# 3_diplom.net
KiCad netlist of a schematic drawn in Altium Designer
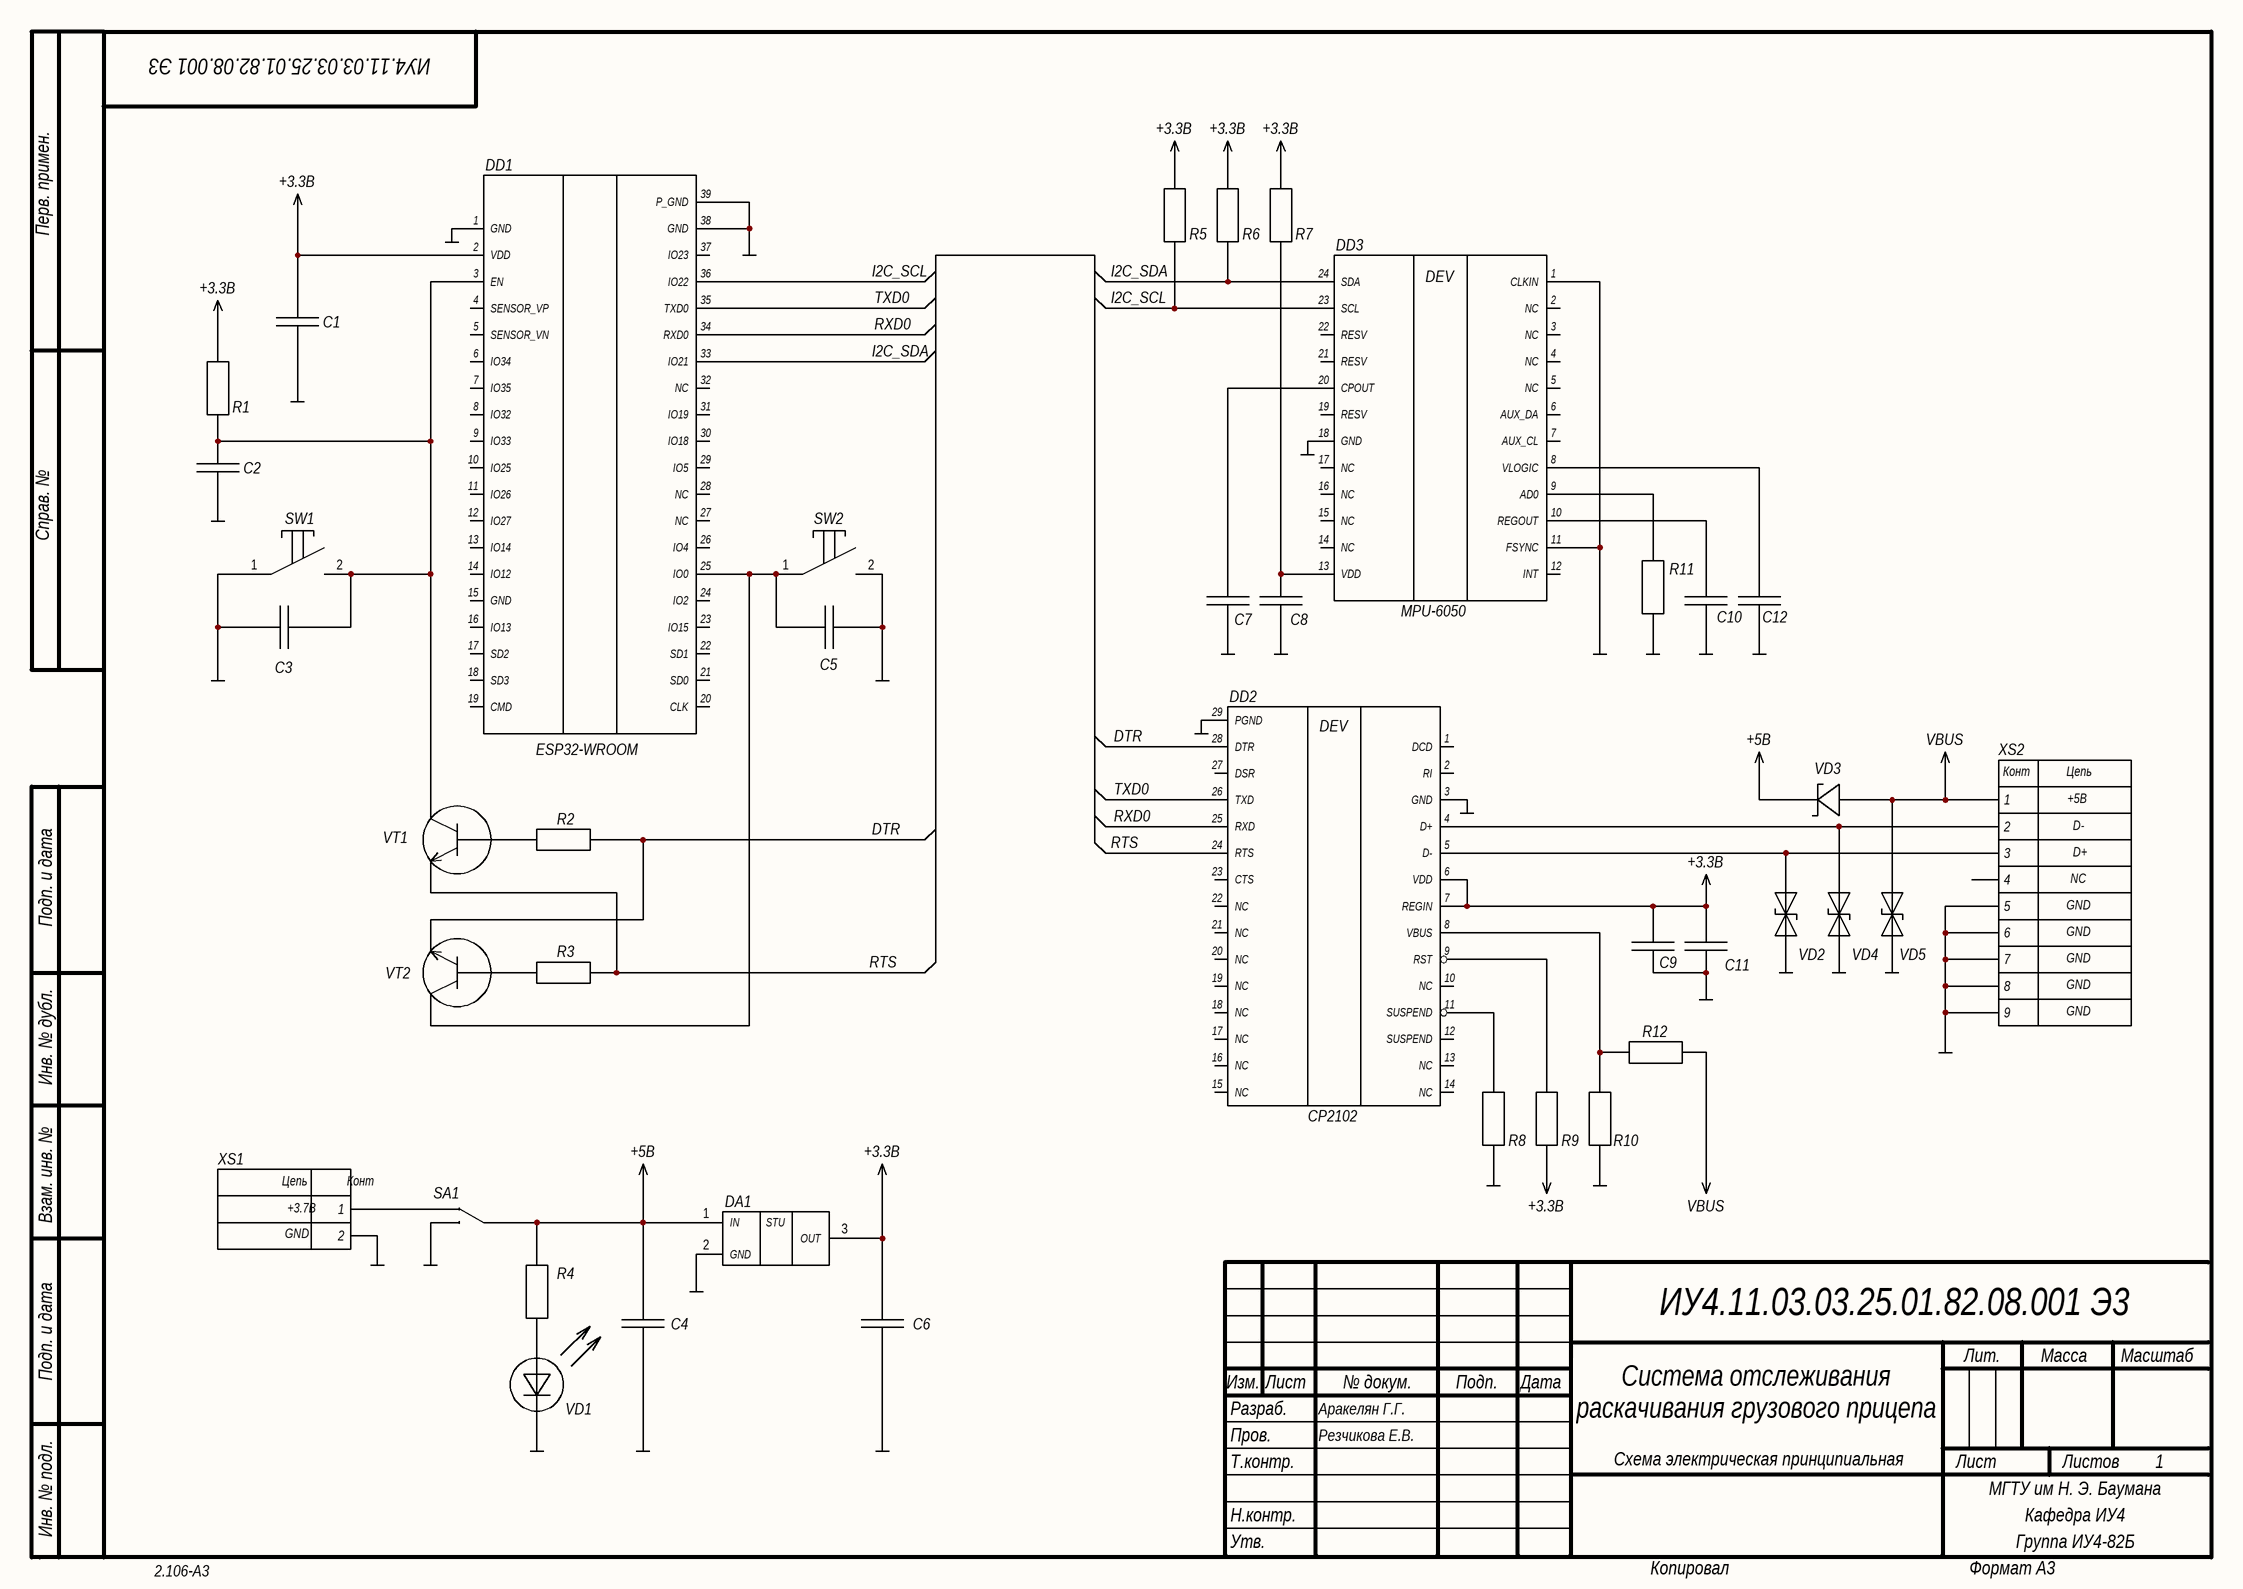
[diagram p0: Э3_diplom.SchDoc]

(export (version "E")
  (design (tool "Eeschema 10.0.6"))
  (components
    (comp (ref "C1") (value "~") (footprint "CAP: 0805") (libsource (lib "diplom") (part "Cap")))
    (comp (ref "C2") (value "~") (footprint "CAP: 0805") (libsource (lib "diplom") (part "Cap")))
    (comp (ref "C3") (value "~") (footprint "CAP: 0805") (libsource (lib "diplom") (part "Cap")))
    (comp (ref "C4") (value "~") (footprint "CAP: 0805") (libsource (lib "diplom") (part "Cap")))
    (comp (ref "C5") (value "~") (footprint "CAP: 0805") (libsource (lib "diplom") (part "Cap")))
    (comp (ref "C6") (value "~") (footprint "CAP: 0805") (libsource (lib "diplom") (part "Cap")))
    (comp (ref "C7") (value "~") (footprint "CAP: 0805") (libsource (lib "diplom") (part "Cap")))
    (comp (ref "C8") (value "~") (footprint "CAP: 0805") (libsource (lib "diplom") (part "Cap")))
    (comp (ref "C9") (value "~") (footprint "CAP: 0805") (libsource (lib "diplom") (part "Cap")))
    (comp (ref "C10") (value "~") (footprint "CAP: 0805") (libsource (lib "diplom") (part "Cap")))
    (comp (ref "C11") (value "~") (footprint "CAP: 0805") (libsource (lib "diplom") (part "Cap")))
    (comp (ref "C12") (value "~") (footprint "CAP: 0805") (libsource (lib "diplom") (part "Cap")))
    (comp (ref "DA1")
      (value "AP2138N")
      (footprint "SOT-23")
      (fields (field (name "PUBLISHER") "Andrew Danich"))
      (libsource (lib "diplom") (part "DC-DC 3.3V"))
    )
    (comp (ref "DD1")
      (value "ESP32-WROOM")
      (footprint "ESP32-S3-WROOM-1-N16R2 - duplicate")
      (libsource (lib "diplom") (part "ESP32-WROVER-B"))
    )
    (comp (ref "DD2") (value "CP2102") (footprint "CP2102") (libsource (lib "diplom") (part "CP2102")))
    (comp (ref "DD3") (value "MPU-6050") (footprint "MPU-6050") (libsource (lib "diplom") (part "MPU-6050")))
    (comp (ref "R1") (value "~") (footprint "RES: 0805") (libsource (lib "diplom") (part "res")))
    (comp (ref "R2") (value "~") (footprint "RES: 0805") (libsource (lib "diplom") (part "res")))
    (comp (ref "R3") (value "~") (footprint "RES: 0805") (libsource (lib "diplom") (part "res")))
    (comp (ref "R4") (value "~") (footprint "RES: 0805") (libsource (lib "diplom") (part "res")))
    (comp (ref "R5") (value "~") (footprint "RES: 0805") (libsource (lib "") (part "res_1")))
    (comp (ref "R6") (value "~") (footprint "RES: 0805") (libsource (lib "") (part "res_1")))
    (comp (ref "R7") (value "~") (footprint "RES: 0805") (libsource (lib "") (part "res_1")))
    (comp (ref "R8") (value "~") (footprint "RES: 0805") (libsource (lib "diplom") (part "res")))
    (comp (ref "R9") (value "~") (footprint "RES: 0805") (libsource (lib "diplom") (part "res")))
    (comp (ref "R10") (value "~") (footprint "RES: 0805") (libsource (lib "diplom") (part "res")))
    (comp (ref "R11") (value "~") (footprint "RES: 0805") (libsource (lib "diplom") (part "res")))
    (comp (ref "R12") (value "~") (footprint "RES: 0805") (libsource (lib "diplom") (part "res")))
    (comp (ref "SA1")
      (value "Switch ON-ON")
      (footprint "PcbLib1:BUT: MTS-102")
      (description "Switch, ON-ON")
      (fields (field (name "MANUFACTURER") "Jietong Switch") (field (name "PARTNUMBER") "MTC-102"))
      (libsource (lib "diplom") (part "Switch ON-ON"))
    )
    (comp (ref "SW1")
      (value "Button")
      (footprint "BUT: SMD 6x6 H4.3")
      (libsource (lib "diplom") (part "Button"))
    )
    (comp (ref "SW2")
      (value "Button")
      (footprint "BUT: SMD 6x6 H4.3")
      (libsource (lib "diplom") (part "Button"))
    )
    (comp (ref "VD1") (value "~") (footprint "LED: 0805") (libsource (lib "diplom") (part "LED")))
    (comp (ref "VD2")
      (value "Suppressor-Bi")
      (footprint "DIOD-523")
      (fields (field (name "PUBLISHER") "Andrew Danich"))
      (libsource (lib "diplom") (part "Suppressor-Bi"))
    )
    (comp (ref "VD3")
      (value "Stab")
      (footprint "BAT760-7")
      (fields (field (name "PUBLISHER") "Andrew Danich"))
      (libsource (lib "diplom") (part "Stab"))
    )
    (comp (ref "VD4")
      (value "Suppressor-Bi")
      (footprint "DIOD-523")
      (fields (field (name "PUBLISHER") "Andrew Danich"))
      (libsource (lib "diplom") (part "Suppressor-Bi"))
    )
    (comp (ref "VD5")
      (value "Suppressor-Bi")
      (footprint "DIOD-523")
      (fields (field (name "PUBLISHER") "Andrew Danich"))
      (libsource (lib "diplom") (part "Suppressor-Bi"))
    )
    (comp (ref "VT1")
      (value "BJT-NPN")
      (footprint "SOT-23")
      (fields (field (name "PUBLISHER") "Andrew Danich"))
      (libsource (lib "diplom") (part "BJT-NPN"))
    )
    (comp (ref "VT2")
      (value "BJT-NPN")
      (footprint "SOT-23")
      (fields (field (name "PUBLISHER") "Andrew Danich"))
      (libsource (lib "diplom") (part "BJT-NPN"))
    )
    (comp (ref "XS1") (value "bat") (footprint "Li-Po") (libsource (lib "diplom") (part "bat")))
    (comp (ref "XS2") (value "USB con") (footprint "MicroUSB") (libsource (lib "diplom") (part "Micro USB")))
  )
  (nets
    (net (code "1") (name "+3.3В") (class "Default")
      (node (ref "C1") (pin "1") (pinfunction "1_1") (pintype "passive"))
      (node (ref "C11") (pin "1") (pinfunction "1_1") (pintype "passive"))
      (node (ref "C6") (pin "1") (pinfunction "1_1") (pintype "passive"))
      (node (ref "C9") (pin "1") (pinfunction "1_1") (pintype "passive"))
      (node (ref "DA1") (pin "3") (pinfunction "OUT_3") (pintype "passive"))
      (node (ref "DD1") (pin "2") (pinfunction "VDD_2") (pintype "passive"))
      (node (ref "DD2") (pin "6") (pinfunction "VDD_6") (pintype "passive"))
      (node (ref "DD2") (pin "7") (pinfunction "REGIN_7") (pintype "passive"))
      (node (ref "R1") (pin "1") (pinfunction "1_1") (pintype "passive"))
      (node (ref "R5") (pin "1") (pinfunction "1_1") (pintype "passive"))
      (node (ref "R6") (pin "1") (pinfunction "1_1") (pintype "passive"))
      (node (ref "R7") (pin "1") (pinfunction "1_1") (pintype "passive"))
      (node (ref "R9") (pin "2") (pinfunction "2_2") (pintype "passive"))
    )
    (net (code "2") (name "+5В") (class "Default")
      (node (ref "C4") (pin "1") (pinfunction "1_1") (pintype "passive"))
      (node (ref "DA1") (pin "1") (pinfunction "IN_1") (pintype "passive"))
      (node (ref "R4") (pin "1") (pinfunction "1_1") (pintype "passive"))
      (node (ref "SA1") (pin "2") (pinfunction "PIN0_2") (pintype "passive"))
      (node (ref "VD3") (pin "2") (pinfunction "К_2") (pintype "passive"))
    )
    (net (code "3") (name "/DTR") (class "Default")
      (node (ref "DD2") (pin "28") (pinfunction "DTR_28") (pintype "passive"))
      (node (ref "R2") (pin "1") (pinfunction "1_1") (pintype "passive"))
      (node (ref "VT2") (pin "3") (pinfunction "Э_3") (pintype "passive"))
    )
    (net (code "4") (name "/I2C_SCL") (class "Default")
      (node (ref "DD1") (pin "36") (pinfunction "IO22_36") (pintype "passive"))
      (node (ref "DD3") (pin "23") (pinfunction "SCL_23") (pintype "passive"))
      (node (ref "R5") (pin "2") (pinfunction "2_2") (pintype "passive"))
    )
    (net (code "5") (name "/I2C_SDA") (class "Default")
      (node (ref "DD1") (pin "33") (pinfunction "IO21_33") (pintype "passive"))
      (node (ref "DD3") (pin "24") (pinfunction "SDA_24") (pintype "passive"))
      (node (ref "R6") (pin "2") (pinfunction "2_2") (pintype "passive"))
    )
    (net (code "6") (name "/RTS") (class "Default")
      (node (ref "DD2") (pin "24") (pinfunction "RTS_24") (pintype "passive"))
      (node (ref "R3") (pin "1") (pinfunction "1_1") (pintype "passive"))
      (node (ref "VT1") (pin "3") (pinfunction "Э_3") (pintype "passive"))
    )
    (net (code "7") (name "/RXD0") (class "Default")
      (node (ref "DD1") (pin "34") (pinfunction "RXD0_34") (pintype "passive"))
      (node (ref "DD2") (pin "25") (pinfunction "RXD_25") (pintype "passive"))
    )
    (net (code "8") (name "/TXD0") (class "Default")
      (node (ref "DD1") (pin "35") (pinfunction "TXD0_35") (pintype "passive"))
      (node (ref "DD2") (pin "26") (pinfunction "TXD_26") (pintype "passive"))
    )
    (net (code "9") (name "GND") (class "Default")
      (node (ref "C1") (pin "2") (pinfunction "2_2") (pintype "passive"))
      (node (ref "C10") (pin "2") (pinfunction "2_2") (pintype "passive"))
      (node (ref "C11") (pin "2") (pinfunction "2_2") (pintype "passive"))
      (node (ref "C12") (pin "2") (pinfunction "2_2") (pintype "passive"))
      (node (ref "C2") (pin "2") (pinfunction "2_2") (pintype "passive"))
      (node (ref "C3") (pin "1") (pinfunction "1_1") (pintype "passive"))
      (node (ref "C4") (pin "2") (pinfunction "2_2") (pintype "passive"))
      (node (ref "C5") (pin "2") (pinfunction "2_2") (pintype "passive"))
      (node (ref "C6") (pin "2") (pinfunction "2_2") (pintype "passive"))
      (node (ref "C7") (pin "2") (pinfunction "2_2") (pintype "passive"))
      (node (ref "C8") (pin "2") (pinfunction "2_2") (pintype "passive"))
      (node (ref "C9") (pin "2") (pinfunction "2_2") (pintype "passive"))
      (node (ref "DA1") (pin "2") (pinfunction "GND_2") (pintype "passive"))
      (node (ref "DD1") (pin "1") (pinfunction "GND_1") (pintype "passive"))
      (node (ref "DD1") (pin "38") (pinfunction "GND_38") (pintype "passive"))
      (node (ref "DD1") (pin "39") (pinfunction "P_GND_39") (pintype "passive"))
      (node (ref "DD2") (pin "29") (pinfunction "PGND_29") (pintype "passive"))
      (node (ref "DD2") (pin "3") (pinfunction "GND_3") (pintype "passive"))
      (node (ref "DD3") (pin "1") (pinfunction "CLKIN_1") (pintype "passive"))
      (node (ref "DD3") (pin "11") (pinfunction "FSYNC_11") (pintype "passive"))
      (node (ref "DD3") (pin "18") (pinfunction "GND_18") (pintype "passive"))
      (node (ref "R10") (pin "2") (pinfunction "2_2") (pintype "passive"))
      (node (ref "R11") (pin "2") (pinfunction "2_2") (pintype "passive"))
      (node (ref "R8") (pin "2") (pinfunction "2_2") (pintype "passive"))
      (node (ref "SA1") (pin "3") (pinfunction "PIN1_3") (pintype "passive"))
      (node (ref "SW1") (pin "1") (pinfunction "1_1") (pintype "passive"))
      (node (ref "SW2") (pin "2") (pinfunction "1_2") (pintype "passive"))
      (node (ref "VD1") (pin "2") (pinfunction "C_2") (pintype "passive"))
      (node (ref "VD2") (pin "2") (pinfunction "К_2") (pintype "passive"))
      (node (ref "VD4") (pin "2") (pinfunction "К_2") (pintype "passive"))
      (node (ref "VD5") (pin "2") (pinfunction "К_2") (pintype "passive"))
      (node (ref "XS1") (pin "2") (pinfunction "2_2") (pintype "passive"))
      (node (ref "XS2") (pin "5") (pinfunction "5_5") (pintype "passive"))
      (node (ref "XS2") (pin "6") (pinfunction "9_6") (pintype "passive"))
    )
    (net (code "10") (name "Net-(DD1-EN)") (class "Default")
      (node (ref "C2") (pin "1") (pinfunction "1_1") (pintype "passive"))
      (node (ref "C3") (pin "2") (pinfunction "2_2") (pintype "passive"))
      (node (ref "DD1") (pin "3") (pinfunction "EN_3") (pintype "passive"))
      (node (ref "R1") (pin "2") (pinfunction "2_2") (pintype "passive"))
      (node (ref "SW1") (pin "2") (pinfunction "1_2") (pintype "passive"))
      (node (ref "VT1") (pin "2") (pinfunction "К_2") (pintype "passive"))
    )
    (net (code "11") (name "Net-(DD1-IO0)") (class "Default")
      (node (ref "C5") (pin "1") (pinfunction "1_1") (pintype "passive"))
      (node (ref "DD1") (pin "25") (pinfunction "IO0_25") (pintype "passive"))
      (node (ref "SW2") (pin "1") (pinfunction "1_1") (pintype "passive"))
      (node (ref "VT2") (pin "2") (pinfunction "К_2") (pintype "passive"))
    )
    (net (code "12") (name "Net-(DD2-D+)") (class "Default")
      (node (ref "DD2") (pin "4") (pinfunction "D+_4") (pintype "passive"))
      (node (ref "VD4") (pin "1") (pinfunction "А_1") (pintype "passive"))
      (node (ref "XS2") (pin "2") (pinfunction "2_2") (pintype "passive"))
    )
    (net (code "13") (name "Net-(DD2-D-)") (class "Default")
      (node (ref "DD2") (pin "5") (pinfunction "D-_5") (pintype "passive"))
      (node (ref "VD2") (pin "1") (pinfunction "А_1") (pintype "passive"))
      (node (ref "XS2") (pin "3") (pinfunction "3_3") (pintype "passive"))
    )
    (net (code "14") (name "Net-(DD2-RST)") (class "Default")
      (node (ref "DD2") (pin "9") (pinfunction "RST_9") (pintype "passive"))
      (node (ref "R9") (pin "1") (pinfunction "1_1") (pintype "passive"))
    )
    (net (code "15") (name "Net-(DD2-SUSPEND-Pad11)") (class "Default")
      (node (ref "DD2") (pin "11") (pinfunction "SUSPEND_11") (pintype "passive"))
      (node (ref "R8") (pin "1") (pinfunction "1_1") (pintype "passive"))
    )
    (net (code "16") (name "Net-(DD2-VBUS)") (class "Default")
      (node (ref "DD2") (pin "8") (pinfunction "VBUS_8") (pintype "passive"))
      (node (ref "R10") (pin "1") (pinfunction "1_1") (pintype "passive"))
      (node (ref "R12") (pin "1") (pinfunction "1_1") (pintype "passive"))
    )
    (net (code "17") (name "Net-(DD3-AD0)") (class "Default")
      (node (ref "DD3") (pin "9") (pinfunction "AD0_9") (pintype "passive"))
      (node (ref "R11") (pin "1") (pinfunction "1_1") (pintype "passive"))
    )
    (net (code "18") (name "Net-(DD3-CPOUT)") (class "Default")
      (node (ref "C7") (pin "1") (pinfunction "1_1") (pintype "passive"))
      (node (ref "DD3") (pin "20") (pinfunction "CPOUT_20") (pintype "passive"))
    )
    (net (code "19") (name "Net-(DD3-REGOUT)") (class "Default")
      (node (ref "C10") (pin "1") (pinfunction "1_1") (pintype "passive"))
      (node (ref "DD3") (pin "10") (pinfunction "REGOUT_10") (pintype "passive"))
    )
    (net (code "20") (name "Net-(DD3-VDD)") (class "Default")
      (node (ref "C8") (pin "1") (pinfunction "1_1") (pintype "passive"))
      (node (ref "DD3") (pin "13") (pinfunction "VDD_13") (pintype "passive"))
      (node (ref "R7") (pin "2") (pinfunction "2_2") (pintype "passive"))
    )
    (net (code "21") (name "Net-(DD3-VLOGIC)") (class "Default")
      (node (ref "C12") (pin "1") (pinfunction "1_1") (pintype "passive"))
      (node (ref "DD3") (pin "8") (pinfunction "VLOGIC_8") (pintype "passive"))
    )
    (net (code "22") (name "Net-(SA1-PIN1-Pad1)") (class "Default")
      (node (ref "SA1") (pin "1") (pinfunction "PIN1_1") (pintype "passive"))
      (node (ref "XS1") (pin "1") (pinfunction "1_1") (pintype "passive"))
    )
    (net (code "23") (name "Net-(VD1-A)") (class "Default")
      (node (ref "R4") (pin "2") (pinfunction "2_2") (pintype "passive"))
      (node (ref "VD1") (pin "1") (pinfunction "A_1") (pintype "passive"))
    )
    (net (code "24") (name "Net-(VT1-Б)") (class "Default")
      (node (ref "R2") (pin "2") (pinfunction "2_2") (pintype "passive"))
      (node (ref "VT1") (pin "1") (pinfunction "Б_1") (pintype "passive"))
    )
    (net (code "25") (name "Net-(VT2-Б)") (class "Default")
      (node (ref "R3") (pin "2") (pinfunction "2_2") (pintype "passive"))
      (node (ref "VT2") (pin "1") (pinfunction "Б_1") (pintype "passive"))
    )
    (net (code "26") (name "VBUS") (class "Default")
      (node (ref "R12") (pin "2") (pinfunction "2_2") (pintype "passive"))
      (node (ref "VD3") (pin "1") (pinfunction "А_1") (pintype "passive"))
      (node (ref "VD5") (pin "1") (pinfunction "А_1") (pintype "passive"))
      (node (ref "XS2") (pin "1") (pinfunction "1_1") (pintype "passive"))
    )
    (net (code "27") (name "unconnected-(DD1-CLK-Pad20)") (class "Default")
      (node (ref "DD1") (pin "20") (pinfunction "CLK_20") (pintype "passive"))
    )
    (net (code "28") (name "unconnected-(DD1-CMD-Pad19)") (class "Default")
      (node (ref "DD1") (pin "19") (pinfunction "CMD_19") (pintype "passive"))
    )
    (net (code "29") (name "unconnected-(DD1-GND-Pad15)") (class "Default")
      (node (ref "DD1") (pin "15") (pinfunction "GND_15") (pintype "passive"))
    )
    (net (code "30") (name "unconnected-(DD1-IO2-Pad24)") (class "Default")
      (node (ref "DD1") (pin "24") (pinfunction "IO2_24") (pintype "passive"))
    )
    (net (code "31") (name "unconnected-(DD1-IO4-Pad26)") (class "Default")
      (node (ref "DD1") (pin "26") (pinfunction "IO4_26") (pintype "passive"))
    )
    (net (code "32") (name "unconnected-(DD1-IO5-Pad29)") (class "Default")
      (node (ref "DD1") (pin "29") (pinfunction "IO5_29") (pintype "passive"))
    )
    (net (code "33") (name "unconnected-(DD1-IO12-Pad14)") (class "Default")
      (node (ref "DD1") (pin "14") (pinfunction "IO12_14") (pintype "passive"))
    )
    (net (code "34") (name "unconnected-(DD1-IO13-Pad16)") (class "Default")
      (node (ref "DD1") (pin "16") (pinfunction "IO13_16") (pintype "passive"))
    )
    (net (code "35") (name "unconnected-(DD1-IO14-Pad13)") (class "Default")
      (node (ref "DD1") (pin "13") (pinfunction "IO14_13") (pintype "passive"))
    )
    (net (code "36") (name "unconnected-(DD1-IO15-Pad23)") (class "Default")
      (node (ref "DD1") (pin "23") (pinfunction "IO15_23") (pintype "passive"))
    )
    (net (code "37") (name "unconnected-(DD1-IO18-Pad30)") (class "Default")
      (node (ref "DD1") (pin "30") (pinfunction "IO18_30") (pintype "passive"))
    )
    (net (code "38") (name "unconnected-(DD1-IO19-Pad31)") (class "Default")
      (node (ref "DD1") (pin "31") (pinfunction "IO19_31") (pintype "passive"))
    )
    (net (code "39") (name "unconnected-(DD1-IO23-Pad37)") (class "Default")
      (node (ref "DD1") (pin "37") (pinfunction "IO23_37") (pintype "passive"))
    )
    (net (code "40") (name "unconnected-(DD1-IO25-Pad10)") (class "Default")
      (node (ref "DD1") (pin "10") (pinfunction "IO25_10") (pintype "passive"))
    )
    (net (code "41") (name "unconnected-(DD1-IO26-Pad11)") (class "Default")
      (node (ref "DD1") (pin "11") (pinfunction "IO26_11") (pintype "passive"))
    )
    (net (code "42") (name "unconnected-(DD1-IO27-Pad12)") (class "Default")
      (node (ref "DD1") (pin "12") (pinfunction "IO27_12") (pintype "passive"))
    )
    (net (code "43") (name "unconnected-(DD1-IO32-Pad8)") (class "Default")
      (node (ref "DD1") (pin "8") (pinfunction "IO32_8") (pintype "passive"))
    )
    (net (code "44") (name "unconnected-(DD1-IO33-Pad9)") (class "Default")
      (node (ref "DD1") (pin "9") (pinfunction "IO33_9") (pintype "passive"))
    )
    (net (code "45") (name "unconnected-(DD1-IO34-Pad6)") (class "Default")
      (node (ref "DD1") (pin "6") (pinfunction "IO34_6") (pintype "passive"))
    )
    (net (code "46") (name "unconnected-(DD1-IO35-Pad7)") (class "Default")
      (node (ref "DD1") (pin "7") (pinfunction "IO35_7") (pintype "passive"))
    )
    (net (code "47") (name "unconnected-(DD1-NC-Pad27)") (class "Default")
      (node (ref "DD1") (pin "27") (pinfunction "NC_27") (pintype "passive"))
    )
    (net (code "48") (name "unconnected-(DD1-NC-Pad28)") (class "Default")
      (node (ref "DD1") (pin "28") (pinfunction "NC_28") (pintype "passive"))
    )
    (net (code "49") (name "unconnected-(DD1-NC-Pad32)") (class "Default")
      (node (ref "DD1") (pin "32") (pinfunction "NC_32") (pintype "passive"))
    )
    (net (code "50") (name "unconnected-(DD1-SD0-Pad21)") (class "Default")
      (node (ref "DD1") (pin "21") (pinfunction "SD0_21") (pintype "passive"))
    )
    (net (code "51") (name "unconnected-(DD1-SD1-Pad22)") (class "Default")
      (node (ref "DD1") (pin "22") (pinfunction "SD1_22") (pintype "passive"))
    )
    (net (code "52") (name "unconnected-(DD1-SD2-Pad17)") (class "Default")
      (node (ref "DD1") (pin "17") (pinfunction "SD2_17") (pintype "passive"))
    )
    (net (code "53") (name "unconnected-(DD1-SD3-Pad18)") (class "Default")
      (node (ref "DD1") (pin "18") (pinfunction "SD3_18") (pintype "passive"))
    )
    (net (code "54") (name "unconnected-(DD1-SENSOR_VN-Pad5)") (class "Default")
      (node (ref "DD1") (pin "5") (pinfunction "SENSOR_VN_5") (pintype "passive"))
    )
    (net (code "55") (name "unconnected-(DD1-SENSOR_VP-Pad4)") (class "Default")
      (node (ref "DD1") (pin "4") (pinfunction "SENSOR_VP_4") (pintype "passive"))
    )
    (net (code "56") (name "unconnected-(DD2-CTS-Pad23)") (class "Default")
      (node (ref "DD2") (pin "23") (pinfunction "CTS_23") (pintype "passive"))
    )
    (net (code "57") (name "unconnected-(DD2-DCD-Pad1)") (class "Default")
      (node (ref "DD2") (pin "1") (pinfunction "DCD_1") (pintype "passive"))
    )
    (net (code "58") (name "unconnected-(DD2-DSR-Pad27)") (class "Default")
      (node (ref "DD2") (pin "27") (pinfunction "DSR_27") (pintype "passive"))
    )
    (net (code "59") (name "unconnected-(DD2-NC-Pad10)") (class "Default")
      (node (ref "DD2") (pin "10") (pinfunction "NC_10") (pintype "passive"))
    )
    (net (code "60") (name "unconnected-(DD2-NC-Pad13)") (class "Default")
      (node (ref "DD2") (pin "13") (pinfunction "NC_13") (pintype "passive"))
    )
    (net (code "61") (name "unconnected-(DD2-NC-Pad14)") (class "Default")
      (node (ref "DD2") (pin "14") (pinfunction "NC_14") (pintype "passive"))
    )
    (net (code "62") (name "unconnected-(DD2-NC-Pad15)") (class "Default")
      (node (ref "DD2") (pin "15") (pinfunction "NC_15") (pintype "passive"))
    )
    (net (code "63") (name "unconnected-(DD2-NC-Pad16)") (class "Default")
      (node (ref "DD2") (pin "16") (pinfunction "NC_16") (pintype "passive"))
    )
    (net (code "64") (name "unconnected-(DD2-NC-Pad17)") (class "Default")
      (node (ref "DD2") (pin "17") (pinfunction "NC_17") (pintype "passive"))
    )
    (net (code "65") (name "unconnected-(DD2-NC-Pad18)") (class "Default")
      (node (ref "DD2") (pin "18") (pinfunction "NC_18") (pintype "passive"))
    )
    (net (code "66") (name "unconnected-(DD2-NC-Pad19)") (class "Default")
      (node (ref "DD2") (pin "19") (pinfunction "NC_19") (pintype "passive"))
    )
    (net (code "67") (name "unconnected-(DD2-NC-Pad20)") (class "Default")
      (node (ref "DD2") (pin "20") (pinfunction "NC_20") (pintype "passive"))
    )
    (net (code "68") (name "unconnected-(DD2-NC-Pad21)") (class "Default")
      (node (ref "DD2") (pin "21") (pinfunction "NC_21") (pintype "passive"))
    )
    (net (code "69") (name "unconnected-(DD2-NC-Pad22)") (class "Default")
      (node (ref "DD2") (pin "22") (pinfunction "NC_22") (pintype "passive"))
    )
    (net (code "70") (name "unconnected-(DD2-RI-Pad2)") (class "Default")
      (node (ref "DD2") (pin "2") (pinfunction "RI_2") (pintype "passive"))
    )
    (net (code "71") (name "unconnected-(DD2-SUSPEND-Pad12)") (class "Default")
      (node (ref "DD2") (pin "12") (pinfunction "SUSPEND_12") (pintype "passive"))
    )
    (net (code "72") (name "unconnected-(DD3-AUX_CL-Pad7)") (class "Default")
      (node (ref "DD3") (pin "7") (pinfunction "AUX_CL_7") (pintype "passive"))
    )
    (net (code "73") (name "unconnected-(DD3-AUX_DA-Pad6)") (class "Default")
      (node (ref "DD3") (pin "6") (pinfunction "AUX_DA_6") (pintype "passive"))
    )
    (net (code "74") (name "unconnected-(DD3-INT-Pad12)") (class "Default")
      (node (ref "DD3") (pin "12") (pinfunction "INT_12") (pintype "passive"))
    )
    (net (code "75") (name "unconnected-(DD3-NC-Pad2)") (class "Default")
      (node (ref "DD3") (pin "2") (pinfunction "NC_2") (pintype "passive"))
    )
    (net (code "76") (name "unconnected-(DD3-NC-Pad3)") (class "Default")
      (node (ref "DD3") (pin "3") (pinfunction "NC_3") (pintype "passive"))
    )
    (net (code "77") (name "unconnected-(DD3-NC-Pad4)") (class "Default")
      (node (ref "DD3") (pin "4") (pinfunction "NC_4") (pintype "passive"))
    )
    (net (code "78") (name "unconnected-(DD3-NC-Pad5)") (class "Default")
      (node (ref "DD3") (pin "5") (pinfunction "NC_5") (pintype "passive"))
    )
    (net (code "79") (name "unconnected-(DD3-NC-Pad14)") (class "Default")
      (node (ref "DD3") (pin "14") (pinfunction "NC_14") (pintype "passive"))
    )
    (net (code "80") (name "unconnected-(DD3-NC-Pad15)") (class "Default")
      (node (ref "DD3") (pin "15") (pinfunction "NC_15") (pintype "passive"))
    )
    (net (code "81") (name "unconnected-(DD3-NC-Pad16)") (class "Default")
      (node (ref "DD3") (pin "16") (pinfunction "NC_16") (pintype "passive"))
    )
    (net (code "82") (name "unconnected-(DD3-NC-Pad17)") (class "Default")
      (node (ref "DD3") (pin "17") (pinfunction "NC_17") (pintype "passive"))
    )
    (net (code "83") (name "unconnected-(DD3-RESV-Pad19)") (class "Default")
      (node (ref "DD3") (pin "19") (pinfunction "RESV_19") (pintype "passive"))
    )
    (net (code "84") (name "unconnected-(DD3-RESV-Pad21)") (class "Default")
      (node (ref "DD3") (pin "21") (pinfunction "RESV_21") (pintype "passive"))
    )
    (net (code "85") (name "unconnected-(DD3-RESV-Pad22)") (class "Default")
      (node (ref "DD3") (pin "22") (pinfunction "RESV_22") (pintype "passive"))
    )
    (net (code "86") (name "unconnected-(XS2-Pad4)") (class "Default")
      (node (ref "XS2") (pin "4") (pinfunction "4_4") (pintype "passive"))
    )
  )
)
